# untitled.net
KiCad netlist of a schematic drawn in EAGLE
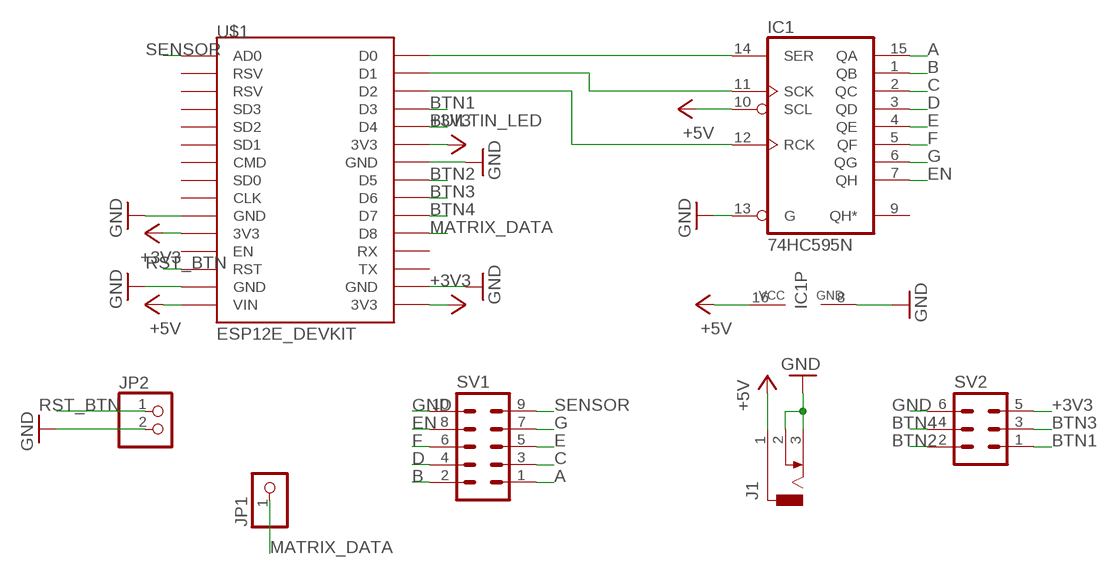
[diagram p0: schematic, sheet 1]

(export (version "E")
  (design (tool "Eeschema 10.0.6"))
  (components
    (comp (ref "IC1")
      (value "74HC595N")
      (footprint "eagle-import:DIL16")
      (libsource (lib "eagle-import") (part "74595NHC"))
    )
    (comp (ref "J1")
      (value "DCJ0303")
      (footprint "eagle-import:DCJ0303")
      (libsource (lib "eagle-import") (part "DCJ0303"))
    )
    (comp (ref "JP1")
      (value "PINHD-1X1")
      (footprint "eagle-import:1X01")
      (libsource (lib "eagle-import") (part "PINHD-1X1"))
    )
    (comp (ref "JP2")
      (value "PINHD-1X2")
      (footprint "eagle-import:1X02")
      (libsource (lib "eagle-import") (part "PINHD-1X2"))
    )
    (comp (ref "SV1")
      (value "ML10")
      (footprint "eagle-import:ML10")
      (libsource (lib "eagle-import") (part "ML10"))
    )
    (comp (ref "SV2")
      (value "ML6")
      (footprint "eagle-import:ML6")
      (libsource (lib "eagle-import") (part "ML6"))
    )
    (comp (ref "U$1")
      (value "ESP12E_DEVKIT")
      (footprint "eagle-import:ESP12E_DEVKIT")
      (libsource (lib "eagle-import") (part "ESP12E_DEVKIT"))
    )
  )
  (nets
    (net (code "1") (name "+3V3") (class "Default")
      (node (ref "SV2") (pin "5") (pinfunction "5_5") (pintype "passive"))
      (node (ref "U$1") (pin "3V3@0") (pinfunction "3V3_3V3@0") (pintype "bidirectional"))
      (node (ref "U$1") (pin "3V3@1") (pinfunction "3V3_3V3@1") (pintype "bidirectional"))
      (node (ref "U$1") (pin "3V3@2") (pinfunction "3V3_3V3@2") (pintype "bidirectional"))
    )
    (net (code "2") (name "+5V") (class "Default")
      (node (ref "IC1") (pin "10") (pinfunction "SCL_10") (pintype "input"))
      (node (ref "IC1") (pin "16") (pinfunction "VCC_16") (pintype "power_in"))
      (node (ref "J1") (pin "1") (pinfunction "1_1") (pintype "passive"))
      (node (ref "U$1") (pin "VIN") (pinfunction "VIN_VIN") (pintype "bidirectional"))
    )
    (net (code "3") (name "/A") (class "Default")
      (node (ref "IC1") (pin "15") (pinfunction "QA_15") (pintype "tri_state"))
      (node (ref "SV1") (pin "1") (pinfunction "1_1") (pintype "passive"))
    )
    (net (code "4") (name "/B") (class "Default")
      (node (ref "IC1") (pin "1") (pinfunction "QB_1") (pintype "tri_state"))
      (node (ref "SV1") (pin "2") (pinfunction "2_2") (pintype "passive"))
    )
    (net (code "5") (name "/BTN1") (class "Default")
      (node (ref "SV2") (pin "1") (pinfunction "1_1") (pintype "passive"))
      (node (ref "U$1") (pin "D3") (pinfunction "D3_D3") (pintype "bidirectional"))
    )
    (net (code "6") (name "/BTN2") (class "Default")
      (node (ref "SV2") (pin "2") (pinfunction "2_2") (pintype "passive"))
      (node (ref "U$1") (pin "D5") (pinfunction "D5_D5") (pintype "bidirectional"))
    )
    (net (code "7") (name "/BTN3") (class "Default")
      (node (ref "SV2") (pin "3") (pinfunction "3_3") (pintype "passive"))
      (node (ref "U$1") (pin "D6") (pinfunction "D6_D6") (pintype "bidirectional"))
    )
    (net (code "8") (name "/BTN4") (class "Default")
      (node (ref "SV2") (pin "4") (pinfunction "4_4") (pintype "passive"))
      (node (ref "U$1") (pin "D7") (pinfunction "D7_D7") (pintype "bidirectional"))
    )
    (net (code "9") (name "/BUILTIN_LED") (class "Default")
      (node (ref "U$1") (pin "D4") (pinfunction "D4_D4") (pintype "bidirectional"))
    )
    (net (code "10") (name "/C") (class "Default")
      (node (ref "IC1") (pin "2") (pinfunction "QC_2") (pintype "tri_state"))
      (node (ref "SV1") (pin "3") (pinfunction "3_3") (pintype "passive"))
    )
    (net (code "11") (name "/D") (class "Default")
      (node (ref "IC1") (pin "3") (pinfunction "QD_3") (pintype "tri_state"))
      (node (ref "SV1") (pin "4") (pinfunction "4_4") (pintype "passive"))
    )
    (net (code "12") (name "/E") (class "Default")
      (node (ref "IC1") (pin "4") (pinfunction "QE_4") (pintype "tri_state"))
      (node (ref "SV1") (pin "5") (pinfunction "5_5") (pintype "passive"))
    )
    (net (code "13") (name "/EN") (class "Default")
      (node (ref "IC1") (pin "7") (pinfunction "QH_7") (pintype "tri_state"))
      (node (ref "SV1") (pin "8") (pinfunction "8_8") (pintype "passive"))
    )
    (net (code "14") (name "/F") (class "Default")
      (node (ref "IC1") (pin "5") (pinfunction "QF_5") (pintype "tri_state"))
      (node (ref "SV1") (pin "6") (pinfunction "6_6") (pintype "passive"))
    )
    (net (code "15") (name "/G") (class "Default")
      (node (ref "IC1") (pin "6") (pinfunction "QG_6") (pintype "tri_state"))
      (node (ref "SV1") (pin "7") (pinfunction "7_7") (pintype "passive"))
    )
    (net (code "16") (name "/MATRIX_DATA") (class "Default")
      (node (ref "JP1") (pin "1") (pinfunction "1_1") (pintype "passive"))
      (node (ref "U$1") (pin "D8") (pinfunction "D8_D8") (pintype "bidirectional"))
    )
    (net (code "17") (name "/RST_BTN") (class "Default")
      (node (ref "JP2") (pin "1") (pinfunction "1_1") (pintype "passive"))
      (node (ref "U$1") (pin "RST") (pinfunction "RST_RST") (pintype "bidirectional"))
    )
    (net (code "18") (name "/SENSOR") (class "Default")
      (node (ref "SV1") (pin "9") (pinfunction "9_9") (pintype "passive"))
      (node (ref "U$1") (pin "AD0") (pinfunction "AD0_AD0") (pintype "bidirectional"))
    )
    (net (code "19") (name "GND") (class "Default")
      (node (ref "IC1") (pin "13") (pinfunction "G_13") (pintype "input"))
      (node (ref "IC1") (pin "8") (pinfunction "GND_8") (pintype "power_in"))
      (node (ref "J1") (pin "2") (pinfunction "2_2") (pintype "passive"))
      (node (ref "J1") (pin "3") (pinfunction "3_3") (pintype "passive"))
      (node (ref "JP2") (pin "2") (pinfunction "2_2") (pintype "passive"))
      (node (ref "SV1") (pin "10") (pinfunction "10_10") (pintype "passive"))
      (node (ref "SV2") (pin "6") (pinfunction "6_6") (pintype "passive"))
      (node (ref "U$1") (pin "GND@0") (pinfunction "GND_GND@0") (pintype "bidirectional"))
      (node (ref "U$1") (pin "GND@1") (pinfunction "GND_GND@1") (pintype "bidirectional"))
      (node (ref "U$1") (pin "GND@2") (pinfunction "GND_GND@2") (pintype "bidirectional"))
      (node (ref "U$1") (pin "GND@3") (pinfunction "GND_GND@3") (pintype "bidirectional"))
    )
    (net (code "20") (name "Net-(IC1A-RCK)") (class "Default")
      (node (ref "IC1") (pin "12") (pinfunction "RCK_12") (pintype "input"))
      (node (ref "U$1") (pin "D2") (pinfunction "D2_D2") (pintype "bidirectional"))
    )
    (net (code "21") (name "Net-(IC1A-SCK)") (class "Default")
      (node (ref "IC1") (pin "11") (pinfunction "SCK_11") (pintype "input"))
      (node (ref "U$1") (pin "D1") (pinfunction "D1_D1") (pintype "bidirectional"))
    )
    (net (code "22") (name "Net-(IC1A-SER)") (class "Default")
      (node (ref "IC1") (pin "14") (pinfunction "SER_14") (pintype "input"))
      (node (ref "U$1") (pin "D0") (pinfunction "D0_D0") (pintype "bidirectional"))
    )
    (net (code "23") (name "unconnected-(IC1A-QH*-Pad9)") (class "Default")
      (node (ref "IC1") (pin "9") (pinfunction "QH*_9") (pintype "tri_state"))
    )
    (net (code "24") (name "unconnected-(U$1-PadCLK)") (class "Default")
      (node (ref "U$1") (pin "CLK") (pinfunction "CLK_CLK") (pintype "bidirectional"))
    )
    (net (code "25") (name "unconnected-(U$1-PadCMD)") (class "Default")
      (node (ref "U$1") (pin "CMD") (pinfunction "CMD_CMD") (pintype "bidirectional"))
    )
    (net (code "26") (name "unconnected-(U$1-PadEN)") (class "Default")
      (node (ref "U$1") (pin "EN") (pinfunction "EN_EN") (pintype "bidirectional"))
    )
    (net (code "27") (name "unconnected-(U$1-PadRX)") (class "Default")
      (node (ref "U$1") (pin "RX") (pinfunction "RX_RX") (pintype "bidirectional"))
    )
    (net (code "28") (name "unconnected-(U$1-PadSD0)") (class "Default")
      (node (ref "U$1") (pin "SD0") (pinfunction "SD0_SD0") (pintype "bidirectional"))
    )
    (net (code "29") (name "unconnected-(U$1-PadSD1)") (class "Default")
      (node (ref "U$1") (pin "SD1") (pinfunction "SD1_SD1") (pintype "bidirectional"))
    )
    (net (code "30") (name "unconnected-(U$1-PadSD2)") (class "Default")
      (node (ref "U$1") (pin "SD2") (pinfunction "SD2_SD2") (pintype "bidirectional"))
    )
    (net (code "31") (name "unconnected-(U$1-PadSD3)") (class "Default")
      (node (ref "U$1") (pin "SD3") (pinfunction "SD3_SD3") (pintype "bidirectional"))
    )
    (net (code "32") (name "unconnected-(U$1-PadTX)") (class "Default")
      (node (ref "U$1") (pin "TX") (pinfunction "TX_TX") (pintype "bidirectional"))
    )
    (net (code "33") (name "unconnected-(U$1-RSV-PadRSV@0)") (class "Default")
      (node (ref "U$1") (pin "RSV@0") (pinfunction "RSV_RSV@0") (pintype "bidirectional"))
    )
    (net (code "34") (name "unconnected-(U$1-RSV-PadRSV@1)") (class "Default")
      (node (ref "U$1") (pin "RSV@1") (pinfunction "RSV_RSV@1") (pintype "bidirectional"))
    )
  )
)
